# MAIN.net
KiCad netlist of a schematic drawn in Altium Designer
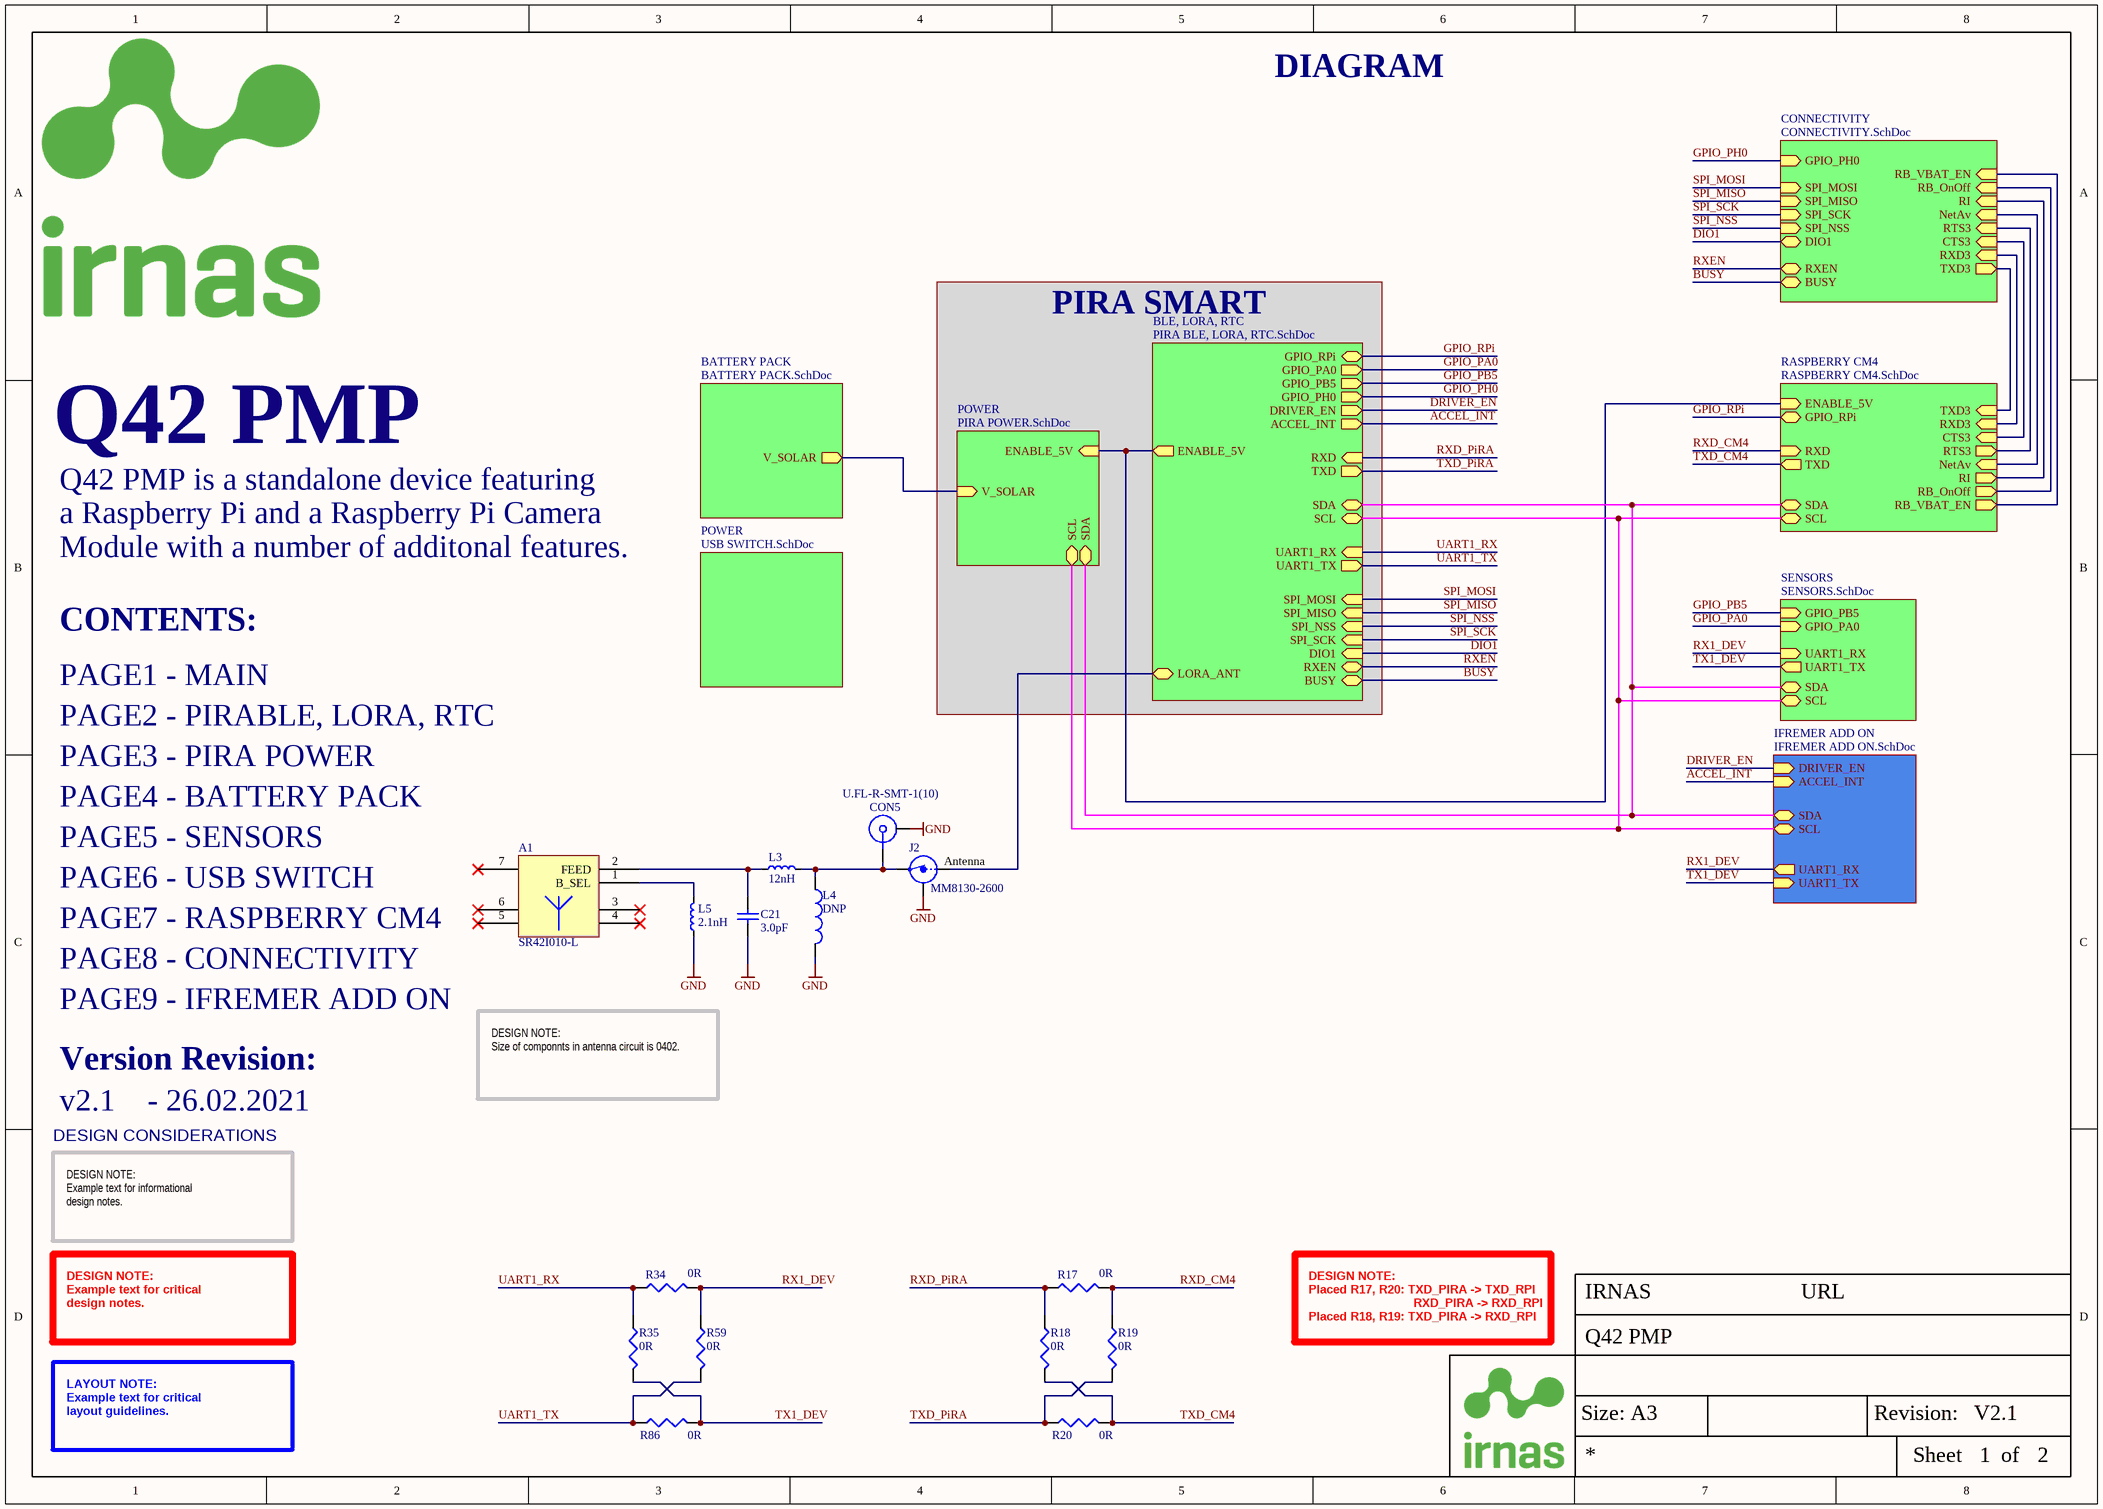
[diagram p0: MAIN.SchDoc]

(export (version "E")
  (design (tool "Eeschema 10.0.6"))
  (components
    (comp (ref "A1")
      (value "SR42I010-L")
      (footprint "SR42I010-L")
      (description "Antenna SMD -4dBi Gain 870MHz/928MHz Automotive 7-Pin SMD T/R")
      (fields (field (name "MANUFACTURER") "Antenova") (field (name "MANUFACTURER PART NUMBER") "SR42I010-R"))
      (libsource (lib "Passive") (part "ANT - SR42I010-R_1"))
    )
    (comp (ref "C21")
      (value "3.0pF")
      (footprint "CAP0402")
      (description "CAP CER 3.0PF 50V C0G/NP0 0402")
      (fields (field (name "Comment") "3.0pF/50V/0402") (field (name "PUBLISHER") "Altium Limited"))
      (libsource (lib "Passive") (part "C - 3.0pF/50V/0402"))
    )
    (comp (ref "CON5")
      (value "U.FL-R-SMT-1(10)")
      (footprint "ufl connector smd")
      (description "RF / Coaxial Connector, U.FL Coaxial, Straight Jack, Surface Mount Vertical, 50 ohm, Brass")
      (fields (field (name "MANUFACTURER") "Hirose"))
      (libsource (lib "Connectors") (part "U.FL-R-SMT-1(10)"))
    )
    (comp (ref "J2")
      (value "MM8130-2600")
      (footprint "COAXIAL-SWF")
      (description "Coaxial Connector with Switch")
      (fields
        (field (name "MANUFACTURER") "Murata")
        (field (name "2ND SOURCE PART NUMBER") "81-MM8130-2600RA2")
        (field (name "PUBLISHER") "Nordic Semiconductor")
      )
      (libsource (lib "Connectors") (part "Coaxial-Internal-SW"))
    )
    (comp (ref "L3")
      (value "12nH")
      (footprint "IND0402")
      (description "IND 12NH 500MA 280 MOHM")
      (fields (field (name "Comment") "10nH/0402") (field (name "PUBLISHER") "Altium Limited"))
      (libsource (lib "Passive") (part "L - 12nH/500mA/0402"))
    )
    (comp (ref "L4")
      (value "DNP")
      (footprint "IND0402")
      (description "Inductor RF Chip Multi-Layer 4.3nH 0.3nH 100MHz 8Q-Factor Air 300mA 210mOhm DCR 0402 Paper T/R")
      (fields
        (field (name "MANUFACTURER") "Murata")
        (field (name "MANUFACTURER PART NUMBER") "LQG15HN4N3S02D")
      )
      (libsource (lib "Passive") (part "L - 4.3nH/0402"))
    )
    (comp (ref "L5")
      (value "2.1nH")
      (footprint "IND0402")
      (description "Multilayer Inductor, AEC-Q200, 2.1 nH, 0.06 ohm, 8 GHz, 1 A, 0402 [1005 Metric], LQG15WH_02 Series")
      (libsource (lib "Passive") (part "L - 2.1nH/0402"))
    )
    (comp (ref "R17")
      (value "0R")
      (footprint "RES0603")
      (description "BOURNS - CR0603-J/-000ELF - RES, THICK FILM, 0R, 5%, 0.1W, 0603")
      (fields
        (field (name "MANUFACTURER") "BOURNS")
        (field (name "MANUFACTURER PART NUMBER") "CR0603-J/-000ELF")
      )
      (libsource (lib "Passive") (part "R - 0R"))
    )
    (comp (ref "R18")
      (value "0R")
      (footprint "RES0603")
      (description "BOURNS - CR0603-J/-000ELF - RES, THICK FILM, 0R, 5%, 0.1W, 0603")
      (fields
        (field (name "MANUFACTURER") "BOURNS")
        (field (name "MANUFACTURER PART NUMBER") "CR0603-J/-000ELF")
      )
      (libsource (lib "Passive") (part "R - 0R"))
    )
    (comp (ref "R19")
      (value "0R")
      (footprint "RES0603")
      (description "BOURNS - CR0603-J/-000ELF - RES, THICK FILM, 0R, 5%, 0.1W, 0603")
      (fields
        (field (name "MANUFACTURER") "BOURNS")
        (field (name "MANUFACTURER PART NUMBER") "CR0603-J/-000ELF")
      )
      (libsource (lib "Passive") (part "R - 0R"))
    )
    (comp (ref "R20")
      (value "0R")
      (footprint "RES0603")
      (description "BOURNS - CR0603-J/-000ELF - RES, THICK FILM, 0R, 5%, 0.1W, 0603")
      (fields
        (field (name "MANUFACTURER") "BOURNS")
        (field (name "MANUFACTURER PART NUMBER") "CR0603-J/-000ELF")
      )
      (libsource (lib "Passive") (part "R - 0R"))
    )
    (comp (ref "R34")
      (value "0R")
      (footprint "RES0603")
      (description "BOURNS - CR0603-J/-000ELF - RES, THICK FILM, 0R, 5%, 0.1W, 0603")
      (fields
        (field (name "MANUFACTURER") "BOURNS")
        (field (name "MANUFACTURER PART NUMBER") "CR0603-J/-000ELF")
      )
      (libsource (lib "Passive") (part "R - 0R"))
    )
    (comp (ref "R35")
      (value "0R")
      (footprint "RES0603")
      (description "BOURNS - CR0603-J/-000ELF - RES, THICK FILM, 0R, 5%, 0.1W, 0603")
      (fields
        (field (name "MANUFACTURER") "BOURNS")
        (field (name "MANUFACTURER PART NUMBER") "CR0603-J/-000ELF")
      )
      (libsource (lib "Passive") (part "R - 0R"))
    )
    (comp (ref "R59")
      (value "0R")
      (footprint "RES0603")
      (description "BOURNS - CR0603-J/-000ELF - RES, THICK FILM, 0R, 5%, 0.1W, 0603")
      (fields
        (field (name "MANUFACTURER") "BOURNS")
        (field (name "MANUFACTURER PART NUMBER") "CR0603-J/-000ELF")
      )
      (libsource (lib "Passive") (part "R - 0R"))
    )
    (comp (ref "R86")
      (value "0R")
      (footprint "RES0603")
      (description "BOURNS - CR0603-J/-000ELF - RES, THICK FILM, 0R, 5%, 0.1W, 0603")
      (fields
        (field (name "MANUFACTURER") "BOURNS")
        (field (name "MANUFACTURER PART NUMBER") "CR0603-J/-000ELF")
      )
      (libsource (lib "Passive") (part "R - 0R"))
    )
  )
  (nets
    (net (code "11") (name "/LORA_ANT") (class "Default")
      (node (ref "J2") (pin "1") (pinfunction "IN_1") (pintype "passive"))
    )
    (net (code "17") (name "/RX1_DEV") (class "Default")
      (node (ref "R34") (pin "2") (pinfunction "2_2") (pintype "passive"))
      (node (ref "R59") (pin "1") (pinfunction "1_1") (pintype "passive"))
    )
    (net (code "19") (name "/RXD_CM4") (class "Default")
      (node (ref "R17") (pin "2") (pinfunction "2_2") (pintype "passive"))
      (node (ref "R19") (pin "1") (pinfunction "1_1") (pintype "passive"))
    )
    (net (code "20") (name "/RXD_PiRA") (class "Default")
      (node (ref "R17") (pin "1") (pinfunction "1_1") (pintype "passive"))
      (node (ref "R18") (pin "1") (pinfunction "1_1") (pintype "passive"))
    )
    (net (code "28") (name "/TX1_DEV") (class "Default")
      (node (ref "R35") (pin "2") (pinfunction "2_2") (pintype "passive"))
      (node (ref "R86") (pin "2") (pinfunction "2_2") (pintype "passive"))
    )
    (net (code "30") (name "/TXD_CM4") (class "Default")
      (node (ref "R18") (pin "2") (pinfunction "2_2") (pintype "passive"))
      (node (ref "R20") (pin "2") (pinfunction "2_2") (pintype "passive"))
    )
    (net (code "31") (name "/TXD_PiRA") (class "Default")
      (node (ref "R19") (pin "2") (pinfunction "2_2") (pintype "passive"))
      (node (ref "R20") (pin "1") (pinfunction "1_1") (pintype "passive"))
    )
    (net (code "32") (name "/UART1_RX") (class "Default")
      (node (ref "R34") (pin "1") (pinfunction "1_1") (pintype "passive"))
      (node (ref "R35") (pin "1") (pinfunction "1_1") (pintype "passive"))
    )
    (net (code "33") (name "/UART1_TX") (class "Default")
      (node (ref "R59") (pin "2") (pinfunction "2_2") (pintype "passive"))
      (node (ref "R86") (pin "1") (pinfunction "1_1") (pintype "passive"))
    )
    (net (code "35") (name "GND") (class "Default")
      (node (ref "C21") (pin "1") (pinfunction "1_1") (pintype "passive"))
      (node (ref "CON5") (pin "2") (pinfunction "2_2") (pintype "passive"))
      (node (ref "J2") (pin "2") (pinfunction "Shield_2") (pintype "passive"))
      (node (ref "L4") (pin "1") (pinfunction "1_1") (pintype "passive"))
      (node (ref "L5") (pin "1") (pinfunction "1_1") (pintype "passive"))
    )
    (net (code "36") (name "Net-(A1-B_SEL)") (class "Default")
      (node (ref "A1") (pin "1") (pinfunction "B_SEL_1") (pintype "passive"))
      (node (ref "L5") (pin "2") (pinfunction "2_2") (pintype "passive"))
    )
    (net (code "37") (name "Net-(A1-FEED)") (class "Default")
      (node (ref "A1") (pin "2") (pinfunction "FEED_2") (pintype "passive"))
      (node (ref "C21") (pin "2") (pinfunction "2_2") (pintype "passive"))
      (node (ref "L3") (pin "1") (pinfunction "1_1") (pintype "passive"))
    )
    (net (code "38") (name "Net-(J2-OUT)") (class "Default")
      (node (ref "CON5") (pin "1") (pinfunction "1_1") (pintype "open_collector"))
      (node (ref "J2") (pin "3") (pinfunction "OUT_3") (pintype "passive"))
      (node (ref "L3") (pin "2") (pinfunction "2_2") (pintype "passive"))
      (node (ref "L4") (pin "2") (pinfunction "2_2") (pintype "passive"))
    )
    (net (code "39") (name "unconnected-(A1-Pad3)") (class "Default")
      (node (ref "A1") (pin "3") (pintype "passive+no_connect"))
    )
    (net (code "40") (name "unconnected-(A1-Pad4)") (class "Default")
      (node (ref "A1") (pin "4") (pintype "passive+no_connect"))
    )
    (net (code "41") (name "unconnected-(A1-Pad5)") (class "Default")
      (node (ref "A1") (pin "5") (pintype "passive+no_connect"))
    )
    (net (code "42") (name "unconnected-(A1-Pad6)") (class "Default")
      (node (ref "A1") (pin "6") (pintype "passive+no_connect"))
    )
    (net (code "43") (name "unconnected-(A1-Pad7)") (class "Default")
      (node (ref "A1") (pin "7") (pintype "passive+no_connect"))
    )
  )
)
